# SDCard.net
KiCad netlist of a schematic drawn in Altium Designer
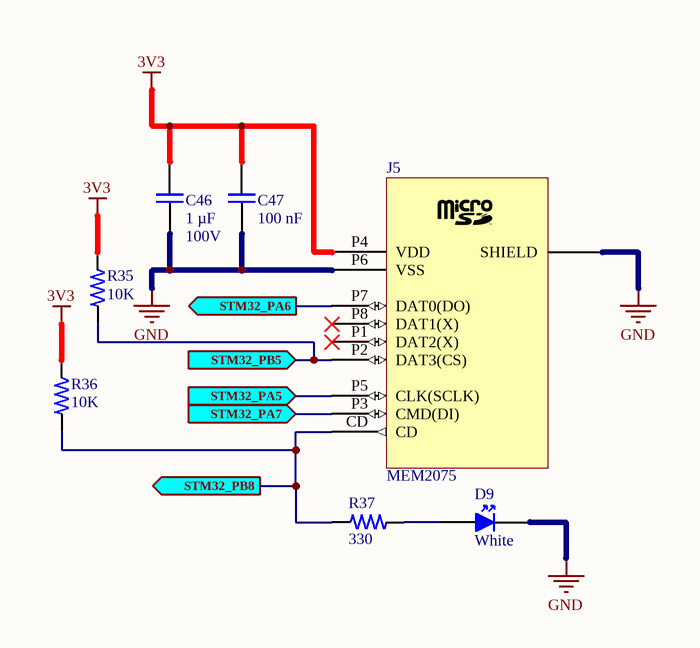
[diagram p0: SDCard.SchDoc]

(export (version "E")
  (design (tool "Eeschema 10.0.6"))
  (components
    (comp (ref "C46")
      (value "1 µF")
      (footprint "MergenElektronik_Capacitors_Ceramics_SMDs_1206_M_NS")
      (description "Mergen Elektronik - Capacitors - Ceramics - SMDs - 1206 - 1 µF - 100V")
      (fields
        (field (name "MANUFACTURER") "Samsung Electro-Mechanics")
        (field (name "TOLERANCE") "±10%")
        (field (name "VOLTAGE RATING") "100V")
      )
      (libsource (lib "MergenElektronik_Capacitors_Ceramics_SMDs") (part "MergenElektronik_Capacitors_Ceramic_SMDs_1µF_100V"))
    )
    (comp (ref "C47")
      (value "100 nF")
      (footprint "MergenElektronik_Capacitors_Ceramics_SMDs_0603_M_NS")
      (description "Mergen Elektronik - Capacitors - Ceramics - SMDs - 0603 - 100 nF - 100V")
      (fields (field (name "MANUFACTURER") "Samsung Electro-Mechanics") (field (name "TOLERANCE") "±10%"))
      (libsource (lib "MergenElektronik_Capacitors_Ceramics_SMDs") (part "MergenElektronik_Capacitors_Ceramic_SMDs_100nF_100V"))
    )
    (comp (ref "D9")
      (value "White")
      (footprint "MergenElektronik_Leds_SMDs_0603_M_NS")
      (description "Mergen Elektronik - Leds - SMDs - White - 0603")
      (fields (field (name "MANUFACTURER") "Harvatek Corporation"))
      (libsource (lib "MergenElektronik_Leds_SMDs") (part "MergenElektronik_LEDs_SMDs_White_0603"))
    )
    (comp (ref "J5")
      (value "MEM2075")
      (footprint "MergenElektronik_Connectors_MicroSD_MEM2075")
      (description "Mergen Elektronik - Connectors - SD Card Connectors - MEM2075")
      (fields (field (name "MANUFACTURER") "GCT"))
      (libsource (lib "MergenElektronik_Connectors_MicroSD") (part "MergenElektronik_Connectors_MicroSD_MEM2075"))
    )
    (comp (ref "R35")
      (value "10K")
      (footprint "MergenElektronik_Resistors_ChipResistors_0603_M_NS")
      (description "Mergen Elektronik - Resistors - Chip Resistors - 0603 - 10K")
      (fields (field (name "MANUFACTURER") "Stackpole Electronics Inc") (field (name "POWER") "1/10W"))
      (libsource (lib "MergenElektronik_Resistors_ChipResistors") (part "MergenElektronik_Resistors_ChipResistors_0603_10K"))
    )
    (comp (ref "R36")
      (value "10K")
      (footprint "MergenElektronik_Resistors_ChipResistors_0603_M_NS")
      (description "Mergen Elektronik - Resistors - Chip Resistors - 0603 - 10K")
      (fields (field (name "MANUFACTURER") "Stackpole Electronics Inc") (field (name "POWER") "1/10W"))
      (libsource (lib "MergenElektronik_Resistors_ChipResistors") (part "MergenElektronik_Resistors_ChipResistors_0603_10K"))
    )
    (comp (ref "R37")
      (value "330")
      (footprint "MergenElektronik_Resistors_ChipResistors_0603_M_NS")
      (description "Mergen Elektronik - Resistors - Chip Resistors - 0603 - 330R")
      (fields (field (name "MANUFACTURER") "Stackpole Electronics Inc") (field (name "POWER") "1/10W"))
      (libsource (lib "MergenElektronik_Resistors_ChipResistors") (part "MergenElektronik_Resistors_ChipResistors_0603_330R"))
    )
  )
  (nets
    (net (code "1") (name "/STM32_PA5") (class "Default")
      (node (ref "J5") (pin "P5") (pinfunction "CLK(SCLK)_P5") (pintype "bidirectional"))
    )
    (net (code "2") (name "/STM32_PA6") (class "Default")
      (node (ref "J5") (pin "P7") (pinfunction "DAT0(DO)_P7") (pintype "bidirectional"))
    )
    (net (code "3") (name "/STM32_PA7") (class "Default")
      (node (ref "J5") (pin "P3") (pinfunction "CMD(DI)_P3") (pintype "bidirectional"))
    )
    (net (code "4") (name "/STM32_PB5") (class "Default")
      (node (ref "J5") (pin "P2") (pinfunction "DAT3(CS)_P2") (pintype "bidirectional"))
      (node (ref "R35") (pin "2") (pinfunction "2_2") (pintype "passive"))
    )
    (net (code "5") (name "/STM32_PB8") (class "Default")
      (node (ref "J5") (pin "CD") (pinfunction "CD_CD") (pintype "output"))
      (node (ref "R36") (pin "2") (pinfunction "2_2") (pintype "passive"))
      (node (ref "R37") (pin "1") (pinfunction "1_1") (pintype "passive"))
    )
    (net (code "6") (name "3V3") (class "Default")
      (node (ref "C46") (pin "1") (pinfunction "1_1") (pintype "passive"))
      (node (ref "C47") (pin "1") (pinfunction "1_1") (pintype "passive"))
      (node (ref "J5") (pin "P4") (pinfunction "VDD_P4") (pintype "power_in"))
      (node (ref "R35") (pin "1") (pinfunction "1_1") (pintype "passive"))
      (node (ref "R36") (pin "1") (pinfunction "1_1") (pintype "passive"))
    )
    (net (code "7") (name "GND") (class "Default")
      (node (ref "C46") (pin "2") (pinfunction "2_2") (pintype "passive"))
      (node (ref "C47") (pin "2") (pinfunction "2_2") (pintype "passive"))
      (node (ref "D9") (pin "2") (pinfunction "KATOT_2") (pintype "passive"))
      (node (ref "J5") (pin "P6") (pinfunction "VSS_P6") (pintype "power_in"))
      (node (ref "J5") (pin "SHIELD") (pinfunction "SHIELD_SHIELD") (pintype "passive"))
    )
    (net (code "8") (name "Net-(D9-ANOT)") (class "Default")
      (node (ref "D9") (pin "1") (pinfunction "ANOT_1") (pintype "passive"))
      (node (ref "R37") (pin "2") (pinfunction "2_2") (pintype "passive"))
    )
    (net (code "9") (name "unconnected-(J5-DAT1(X)-PadP8)") (class "Default")
      (node (ref "J5") (pin "P8") (pinfunction "DAT1(X)_P8") (pintype "bidirectional+no_connect"))
    )
    (net (code "10") (name "unconnected-(J5-DAT2(X)-PadP1)") (class "Default")
      (node (ref "J5") (pin "P1") (pinfunction "DAT2(X)_P1") (pintype "bidirectional+no_connect"))
    )
  )
)
